# splitflap_02.net
KiCad netlist of a schematic drawn in EAGLE
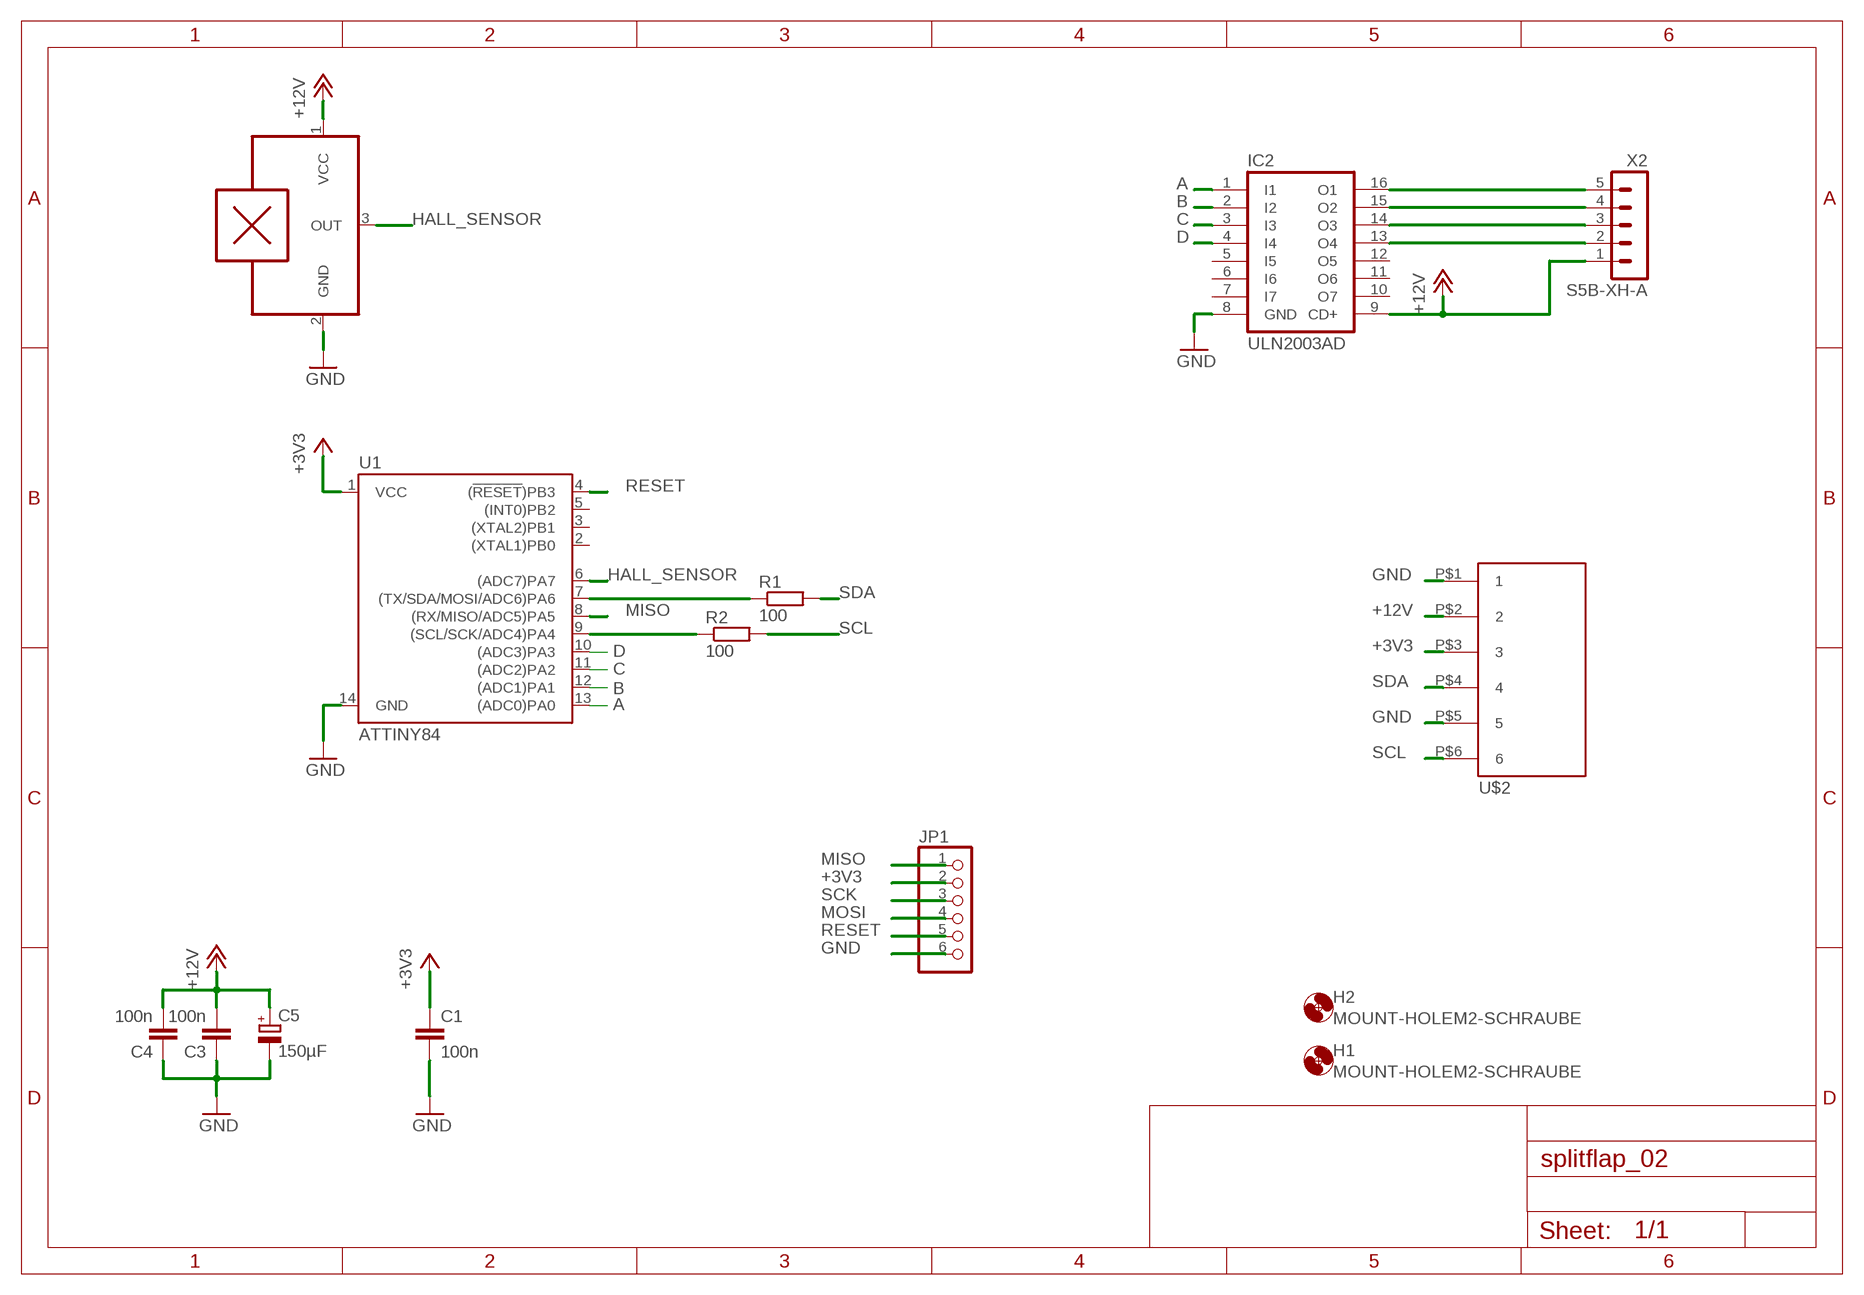
[diagram p0: schematic, sheet 1]

(export (version "E")
  (design (tool "Eeschema 10.0.6"))
  (components
    (comp (ref "C1")
      (value "100n")
      (footprint "eagle-import:C0805")
      (libsource (lib "eagle-import") (part "C-EUC0805"))
    )
    (comp (ref "C3")
      (value "100n")
      (footprint "eagle-import:C0805")
      (libsource (lib "eagle-import") (part "C-EUC0805"))
    )
    (comp (ref "C4")
      (value "100n")
      (footprint "eagle-import:C0805")
      (libsource (lib "eagle-import") (part "C-EUC0805"))
    )
    (comp (ref "C5")
      (value "150µF")
      (footprint "eagle-import:SMC_D")
      (libsource (lib "eagle-import") (part "CPOL-EUSMCD"))
    )
    (comp (ref "H1")
      (value "MOUNT-HOLEM2-SCHRAUBE")
      (footprint "eagle-import:M2-SCHRAUBE")
      (libsource (lib "eagle-import") (part "MOUNT-HOLEM2-SCHRAUBE"))
    )
    (comp (ref "H2")
      (value "MOUNT-HOLEM2-SCHRAUBE")
      (footprint "eagle-import:M2-SCHRAUBE")
      (libsource (lib "eagle-import") (part "MOUNT-HOLEM2-SCHRAUBE"))
    )
    (comp (ref "IC2")
      (value "ULN2003AD")
      (footprint "eagle-import:SO16")
      (libsource (lib "eagle-import") (part "ULN2003AD"))
    )
    (comp (ref "JP1")
      (value "PINHD-1X6M")
      (footprint "eagle-import:1X06M")
      (libsource (lib "eagle-import") (part "PINHD-1X6M"))
    )
    (comp (ref "R1")
      (value "100")
      (footprint "eagle-import:R0805")
      (libsource (lib "eagle-import") (part "R-EU_R0805"))
    )
    (comp (ref "R2")
      (value "100")
      (footprint "eagle-import:R0805")
      (libsource (lib "eagle-import") (part "R-EU_R0805"))
    )
    (comp (ref "U$1")
      (value "A3144")
      (footprint "eagle-import:TO-92-LINE")
      (libsource (lib "eagle-import") (part "A3144"))
    )
    (comp (ref "U$2")
      (value "AMP-MICROMATCH-06")
      (footprint "eagle-import:AMP-MICROMATCH-06")
      (libsource (lib "eagle-import") (part "AMP-MICROMATCH-06"))
    )
    (comp (ref "U1")
      (value "ATTINY84")
      (footprint "eagle-import:SO14")
      (libsource (lib "eagle-import") (part "ATTINY84"))
    )
    (comp (ref "X2")
      (value "S5B-XH-A")
      (footprint "eagle-import:S5B-XH-A")
      (libsource (lib "eagle-import") (part "S5B-XH-A"))
    )
  )
  (nets
    (net (code "1") (name "+3V3") (class "Default")
      (node (ref "C1") (pin "1") (pinfunction "1_1") (pintype "passive"))
      (node (ref "JP1") (pin "2") (pinfunction "2_2") (pintype "passive"))
      (node (ref "U$2") (pin "P$3") (pinfunction "3_P$3") (pintype "bidirectional"))
      (node (ref "U1") (pin "1") (pinfunction "VCC_1") (pintype "bidirectional"))
    )
    (net (code "2") (name "+12V") (class "Default")
      (node (ref "C3") (pin "2") (pinfunction "2_2") (pintype "passive"))
      (node (ref "C4") (pin "2") (pinfunction "2_2") (pintype "passive"))
      (node (ref "C5") (pin "+") (pinfunction "+_+") (pintype "passive"))
      (node (ref "IC2") (pin "9") (pinfunction "CD+_9") (pintype "passive"))
      (node (ref "U$1") (pin "1") (pinfunction "VCC_1") (pintype "power_in"))
      (node (ref "U$2") (pin "P$2") (pinfunction "2_P$2") (pintype "bidirectional"))
      (node (ref "X2") (pin "1") (pinfunction "1_1") (pintype "passive"))
    )
    (net (code "3") (name "/A") (class "Default")
      (node (ref "IC2") (pin "1") (pinfunction "I1_1") (pintype "input"))
      (node (ref "U1") (pin "13") (pinfunction "(ADC0)PA0_13") (pintype "bidirectional"))
    )
    (net (code "4") (name "/B") (class "Default")
      (node (ref "IC2") (pin "2") (pinfunction "I2_2") (pintype "input"))
      (node (ref "U1") (pin "12") (pinfunction "(ADC1)PA1_12") (pintype "bidirectional"))
    )
    (net (code "5") (name "/C") (class "Default")
      (node (ref "IC2") (pin "3") (pinfunction "I3_3") (pintype "input"))
      (node (ref "U1") (pin "11") (pinfunction "(ADC2)PA2_11") (pintype "bidirectional"))
    )
    (net (code "6") (name "/D") (class "Default")
      (node (ref "IC2") (pin "4") (pinfunction "I4_4") (pintype "input"))
      (node (ref "U1") (pin "10") (pinfunction "(ADC3)PA3_10") (pintype "bidirectional"))
    )
    (net (code "7") (name "/HALL_SENSOR") (class "Default")
      (node (ref "U$1") (pin "3") (pinfunction "OUT_3") (pintype "bidirectional"))
      (node (ref "U1") (pin "6") (pinfunction "(ADC7)PA7_6") (pintype "bidirectional"))
    )
    (net (code "8") (name "/MISO") (class "Default")
      (node (ref "JP1") (pin "1") (pinfunction "1_1") (pintype "passive"))
      (node (ref "U1") (pin "8") (pinfunction "(RX/MISO/ADC5)PA5_8") (pintype "bidirectional"))
    )
    (net (code "9") (name "/MOSI") (class "Default")
      (node (ref "JP1") (pin "4") (pinfunction "4_4") (pintype "passive"))
      (node (ref "R1") (pin "1") (pinfunction "1_1") (pintype "passive"))
      (node (ref "U1") (pin "7") (pinfunction "(TX/SDA/MOSI/ADC6)PA6_7") (pintype "bidirectional"))
    )
    (net (code "10") (name "/RESET") (class "Default")
      (node (ref "JP1") (pin "5") (pinfunction "5_5") (pintype "passive"))
      (node (ref "U1") (pin "4") (pinfunction "(~{RESET})PB3_4") (pintype "bidirectional"))
    )
    (net (code "11") (name "/SCK") (class "Default")
      (node (ref "JP1") (pin "3") (pinfunction "3_3") (pintype "passive"))
      (node (ref "R2") (pin "1") (pinfunction "1_1") (pintype "passive"))
      (node (ref "U1") (pin "9") (pinfunction "(SCL/SCK/ADC4)PA4_9") (pintype "bidirectional"))
    )
    (net (code "12") (name "/SCL") (class "Default")
      (node (ref "R2") (pin "2") (pinfunction "2_2") (pintype "passive"))
      (node (ref "U$2") (pin "P$6") (pinfunction "6_P$6") (pintype "bidirectional"))
    )
    (net (code "13") (name "/SDA") (class "Default")
      (node (ref "R1") (pin "2") (pinfunction "2_2") (pintype "passive"))
      (node (ref "U$2") (pin "P$4") (pinfunction "4_P$4") (pintype "bidirectional"))
    )
    (net (code "14") (name "GND") (class "Default")
      (node (ref "C1") (pin "2") (pinfunction "2_2") (pintype "passive"))
      (node (ref "C3") (pin "1") (pinfunction "1_1") (pintype "passive"))
      (node (ref "C4") (pin "1") (pinfunction "1_1") (pintype "passive"))
      (node (ref "C5") (pin "-") (pinfunction "-_-") (pintype "passive"))
      (node (ref "IC2") (pin "8") (pinfunction "GND_8") (pintype "power_in"))
      (node (ref "JP1") (pin "6") (pinfunction "6_6") (pintype "passive"))
      (node (ref "U$1") (pin "2") (pinfunction "GND_2") (pintype "bidirectional"))
      (node (ref "U$2") (pin "P$1") (pinfunction "1_P$1") (pintype "bidirectional"))
      (node (ref "U$2") (pin "P$5") (pinfunction "5_P$5") (pintype "bidirectional"))
      (node (ref "U1") (pin "14") (pinfunction "GND_14") (pintype "bidirectional"))
    )
    (net (code "15") (name "Net-(IC2-O1)") (class "Default")
      (node (ref "IC2") (pin "16") (pinfunction "O1_16") (pintype "open_collector"))
      (node (ref "X2") (pin "5") (pinfunction "5_5") (pintype "passive"))
    )
    (net (code "16") (name "Net-(IC2-O2)") (class "Default")
      (node (ref "IC2") (pin "15") (pinfunction "O2_15") (pintype "open_collector"))
      (node (ref "X2") (pin "4") (pinfunction "4_4") (pintype "passive"))
    )
    (net (code "17") (name "Net-(IC2-O3)") (class "Default")
      (node (ref "IC2") (pin "14") (pinfunction "O3_14") (pintype "open_collector"))
      (node (ref "X2") (pin "3") (pinfunction "3_3") (pintype "passive"))
    )
    (net (code "18") (name "Net-(IC2-O4)") (class "Default")
      (node (ref "IC2") (pin "13") (pinfunction "O4_13") (pintype "open_collector"))
      (node (ref "X2") (pin "2") (pinfunction "2_2") (pintype "passive"))
    )
    (net (code "19") (name "unconnected-(IC2-I5-Pad5)") (class "Default")
      (node (ref "IC2") (pin "5") (pinfunction "I5_5") (pintype "input"))
    )
    (net (code "20") (name "unconnected-(IC2-I6-Pad6)") (class "Default")
      (node (ref "IC2") (pin "6") (pinfunction "I6_6") (pintype "input"))
    )
    (net (code "21") (name "unconnected-(IC2-I7-Pad7)") (class "Default")
      (node (ref "IC2") (pin "7") (pinfunction "I7_7") (pintype "input"))
    )
    (net (code "22") (name "unconnected-(IC2-O5-Pad12)") (class "Default")
      (node (ref "IC2") (pin "12") (pinfunction "O5_12") (pintype "open_collector"))
    )
    (net (code "23") (name "unconnected-(IC2-O6-Pad11)") (class "Default")
      (node (ref "IC2") (pin "11") (pinfunction "O6_11") (pintype "open_collector"))
    )
    (net (code "24") (name "unconnected-(IC2-O7-Pad10)") (class "Default")
      (node (ref "IC2") (pin "10") (pinfunction "O7_10") (pintype "open_collector"))
    )
    (net (code "25") (name "unconnected-(U1-(INT0)PB2-Pad5)") (class "Default")
      (node (ref "U1") (pin "5") (pinfunction "(INT0)PB2_5") (pintype "bidirectional"))
    )
    (net (code "26") (name "unconnected-(U1-(XTAL1)PB0-Pad2)") (class "Default")
      (node (ref "U1") (pin "2") (pinfunction "(XTAL1)PB0_2") (pintype "bidirectional"))
    )
    (net (code "27") (name "unconnected-(U1-(XTAL2)PB1-Pad3)") (class "Default")
      (node (ref "U1") (pin "3") (pinfunction "(XTAL2)PB1_3") (pintype "bidirectional"))
    )
  )
)
